# IndicationBoard.net
KiCad netlist of a schematic drawn in Altium Designer
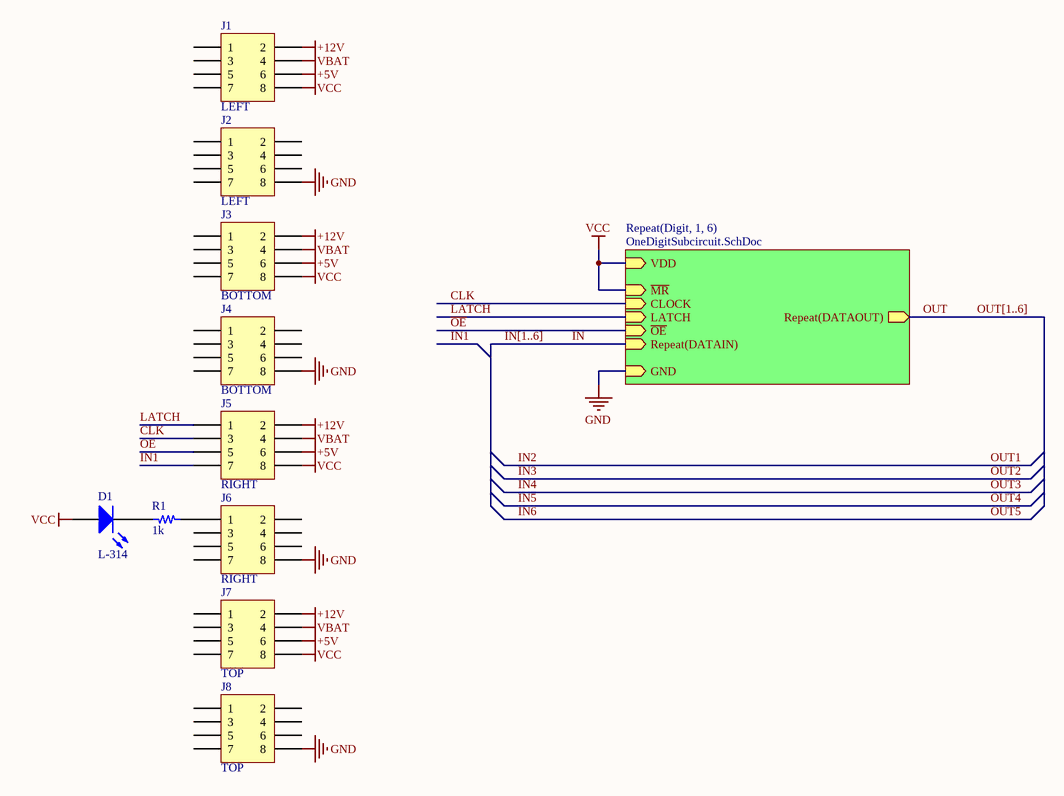
[diagram p0: IndicationBoard.SchDoc]

(export (version "E")
  (design (tool "Eeschema 10.0.6"))
  (components
    (comp (ref "D1")
      (value "L-314")
      (footprint "LED 3mm")
      (description "3-mm LED")
      (fields (field (name "AUTHOR") "oiezhov"))
      (libsource (lib "Library") (part "LED"))
    )
    (comp (ref "J1")
      (value "LEFT")
      (footprint "PBDM-8")
      (description "2x4-pin header, pitch 2.54 mm")
      (fields (field (name "PARTNUMBER") "PBDM-8") (field (name "AUTHOR") "oiezhov"))
      (libsource (lib "Library") (part "8-pin dual row connector"))
    )
    (comp (ref "J2")
      (value "LEFT")
      (footprint "PBDM-8")
      (description "2x4-pin header, pitch 2.54 mm")
      (fields (field (name "PARTNUMBER") "PBDM-8") (field (name "AUTHOR") "oiezhov"))
      (libsource (lib "Library") (part "8-pin dual row connector"))
    )
    (comp (ref "J3")
      (value "BOTTOM")
      (footprint "PBDM-8")
      (description "2x4-pin header, pitch 2.54 mm")
      (fields (field (name "PARTNUMBER") "PBDM-8") (field (name "AUTHOR") "oiezhov"))
      (libsource (lib "Library") (part "8-pin dual row connector"))
    )
    (comp (ref "J4")
      (value "BOTTOM")
      (footprint "PBDM-8")
      (description "2x4-pin header, pitch 2.54 mm")
      (fields (field (name "PARTNUMBER") "PBDM-8") (field (name "AUTHOR") "oiezhov"))
      (libsource (lib "Library") (part "8-pin dual row connector"))
    )
    (comp (ref "J5")
      (value "RIGHT")
      (footprint "PBDM-8")
      (description "2x4-pin header, pitch 2.54 mm")
      (fields (field (name "PARTNUMBER") "PBDM-8") (field (name "AUTHOR") "oiezhov"))
      (libsource (lib "Library") (part "8-pin dual row connector"))
    )
    (comp (ref "J6")
      (value "RIGHT")
      (footprint "PBDM-8")
      (description "2x4-pin header, pitch 2.54 mm")
      (fields (field (name "PARTNUMBER") "PBDM-8") (field (name "AUTHOR") "oiezhov"))
      (libsource (lib "Library") (part "8-pin dual row connector"))
    )
    (comp (ref "J7")
      (value "TOP")
      (footprint "PBDM-8")
      (description "2x4-pin header, pitch 2.54 mm")
      (fields (field (name "PARTNUMBER") "PBDM-8") (field (name "AUTHOR") "oiezhov"))
      (libsource (lib "Library") (part "8-pin dual row connector"))
    )
    (comp (ref "J8")
      (value "TOP")
      (footprint "PBDM-8")
      (description "2x4-pin header, pitch 2.54 mm")
      (fields (field (name "PARTNUMBER") "PBDM-8") (field (name "AUTHOR") "oiezhov"))
      (libsource (lib "Library") (part "8-pin dual row connector"))
    )
    (comp (ref "R1")
      (value "1k")
      (footprint "RES0402")
      (description "Ceramic chip resistor")
      (fields (field (name "PARTNUMBER") "RES0402") (field (name "AUTHOR") "oiezhov"))
      (libsource (lib "Library") (part "Resistor"))
    )
  )
  (nets
    (net (code "2") (name "+5V") (class "Default")
      (node (ref "J1") (pin "6") (pinfunction "6_6") (pintype "passive"))
      (node (ref "J3") (pin "6") (pinfunction "6_6") (pintype "passive"))
      (node (ref "J5") (pin "6") (pinfunction "6_6") (pintype "passive"))
      (node (ref "J7") (pin "6") (pinfunction "6_6") (pintype "passive"))
    )
    (net (code "3") (name "+12V") (class "Default")
      (node (ref "J1") (pin "2") (pinfunction "2_2") (pintype "passive"))
      (node (ref "J3") (pin "2") (pinfunction "2_2") (pintype "passive"))
      (node (ref "J5") (pin "2") (pinfunction "2_2") (pintype "passive"))
      (node (ref "J7") (pin "2") (pinfunction "2_2") (pintype "passive"))
    )
    (net (code "4") (name "/CLK") (class "Default")
      (node (ref "J5") (pin "3") (pinfunction "3_3") (pintype "passive"))
    )
    (net (code "6") (name "/IN1") (class "Default")
      (node (ref "J5") (pin "7") (pinfunction "7_7") (pintype "passive"))
    )
    (net (code "13") (name "/LATCH") (class "Default")
      (node (ref "J5") (pin "1") (pinfunction "1_1") (pintype "passive"))
    )
    (net (code "16") (name "/~{OE}") (class "Default")
      (node (ref "J5") (pin "5") (pinfunction "5_5") (pintype "passive"))
    )
    (net (code "17") (name "GND") (class "Default")
      (node (ref "J2") (pin "8") (pinfunction "8_8") (pintype "passive"))
      (node (ref "J4") (pin "8") (pinfunction "8_8") (pintype "passive"))
      (node (ref "J6") (pin "8") (pinfunction "8_8") (pintype "passive"))
      (node (ref "J8") (pin "8") (pinfunction "8_8") (pintype "passive"))
    )
    (net (code "18") (name "Net-(D1-Pad1)") (class "Default")
      (node (ref "D1") (pin "1") (pinfunction "1_1") (pintype "passive"))
      (node (ref "R1") (pin "1") (pinfunction "1_1") (pintype "passive"))
    )
    (net (code "19") (name "Net-(J6-Pad1)") (class "Default")
      (node (ref "J6") (pin "1") (pinfunction "1_1") (pintype "passive"))
      (node (ref "R1") (pin "2") (pinfunction "2_2") (pintype "passive"))
    )
    (net (code "20") (name "VBAT") (class "Default")
      (node (ref "J1") (pin "4") (pinfunction "4_4") (pintype "passive"))
      (node (ref "J3") (pin "4") (pinfunction "4_4") (pintype "passive"))
      (node (ref "J5") (pin "4") (pinfunction "4_4") (pintype "passive"))
      (node (ref "J7") (pin "4") (pinfunction "4_4") (pintype "passive"))
    )
    (net (code "21") (name "VCC") (class "Default")
      (node (ref "D1") (pin "2") (pinfunction "2_2") (pintype "passive"))
      (node (ref "J1") (pin "8") (pinfunction "8_8") (pintype "passive"))
      (node (ref "J3") (pin "8") (pinfunction "8_8") (pintype "passive"))
      (node (ref "J5") (pin "8") (pinfunction "8_8") (pintype "passive"))
      (node (ref "J7") (pin "8") (pinfunction "8_8") (pintype "passive"))
    )
    (net (code "22") (name "unconnected-(J1-Pad1)") (class "Default")
      (node (ref "J1") (pin "1") (pinfunction "1_1") (pintype "passive"))
    )
    (net (code "23") (name "unconnected-(J1-Pad3)") (class "Default")
      (node (ref "J1") (pin "3") (pinfunction "3_3") (pintype "passive"))
    )
    (net (code "24") (name "unconnected-(J1-Pad5)") (class "Default")
      (node (ref "J1") (pin "5") (pinfunction "5_5") (pintype "passive"))
    )
    (net (code "25") (name "unconnected-(J1-Pad7)") (class "Default")
      (node (ref "J1") (pin "7") (pinfunction "7_7") (pintype "passive"))
    )
    (net (code "26") (name "unconnected-(J2-Pad1)") (class "Default")
      (node (ref "J2") (pin "1") (pinfunction "1_1") (pintype "passive"))
    )
    (net (code "27") (name "unconnected-(J2-Pad2)") (class "Default")
      (node (ref "J2") (pin "2") (pinfunction "2_2") (pintype "passive"))
    )
    (net (code "28") (name "unconnected-(J2-Pad3)") (class "Default")
      (node (ref "J2") (pin "3") (pinfunction "3_3") (pintype "passive"))
    )
    (net (code "29") (name "unconnected-(J2-Pad4)") (class "Default")
      (node (ref "J2") (pin "4") (pinfunction "4_4") (pintype "passive"))
    )
    (net (code "30") (name "unconnected-(J2-Pad5)") (class "Default")
      (node (ref "J2") (pin "5") (pinfunction "5_5") (pintype "passive"))
    )
    (net (code "31") (name "unconnected-(J2-Pad6)") (class "Default")
      (node (ref "J2") (pin "6") (pinfunction "6_6") (pintype "passive"))
    )
    (net (code "32") (name "unconnected-(J2-Pad7)") (class "Default")
      (node (ref "J2") (pin "7") (pinfunction "7_7") (pintype "passive"))
    )
    (net (code "33") (name "unconnected-(J3-Pad1)") (class "Default")
      (node (ref "J3") (pin "1") (pinfunction "1_1") (pintype "passive"))
    )
    (net (code "34") (name "unconnected-(J3-Pad3)") (class "Default")
      (node (ref "J3") (pin "3") (pinfunction "3_3") (pintype "passive"))
    )
    (net (code "35") (name "unconnected-(J3-Pad5)") (class "Default")
      (node (ref "J3") (pin "5") (pinfunction "5_5") (pintype "passive"))
    )
    (net (code "36") (name "unconnected-(J3-Pad7)") (class "Default")
      (node (ref "J3") (pin "7") (pinfunction "7_7") (pintype "passive"))
    )
    (net (code "37") (name "unconnected-(J4-Pad1)") (class "Default")
      (node (ref "J4") (pin "1") (pinfunction "1_1") (pintype "passive"))
    )
    (net (code "38") (name "unconnected-(J4-Pad2)") (class "Default")
      (node (ref "J4") (pin "2") (pinfunction "2_2") (pintype "passive"))
    )
    (net (code "39") (name "unconnected-(J4-Pad3)") (class "Default")
      (node (ref "J4") (pin "3") (pinfunction "3_3") (pintype "passive"))
    )
    (net (code "40") (name "unconnected-(J4-Pad4)") (class "Default")
      (node (ref "J4") (pin "4") (pinfunction "4_4") (pintype "passive"))
    )
    (net (code "41") (name "unconnected-(J4-Pad5)") (class "Default")
      (node (ref "J4") (pin "5") (pinfunction "5_5") (pintype "passive"))
    )
    (net (code "42") (name "unconnected-(J4-Pad6)") (class "Default")
      (node (ref "J4") (pin "6") (pinfunction "6_6") (pintype "passive"))
    )
    (net (code "43") (name "unconnected-(J4-Pad7)") (class "Default")
      (node (ref "J4") (pin "7") (pinfunction "7_7") (pintype "passive"))
    )
    (net (code "44") (name "unconnected-(J6-Pad2)") (class "Default")
      (node (ref "J6") (pin "2") (pinfunction "2_2") (pintype "passive"))
    )
    (net (code "45") (name "unconnected-(J6-Pad3)") (class "Default")
      (node (ref "J6") (pin "3") (pinfunction "3_3") (pintype "passive"))
    )
    (net (code "46") (name "unconnected-(J6-Pad4)") (class "Default")
      (node (ref "J6") (pin "4") (pinfunction "4_4") (pintype "passive"))
    )
    (net (code "47") (name "unconnected-(J6-Pad5)") (class "Default")
      (node (ref "J6") (pin "5") (pinfunction "5_5") (pintype "passive"))
    )
    (net (code "48") (name "unconnected-(J6-Pad6)") (class "Default")
      (node (ref "J6") (pin "6") (pinfunction "6_6") (pintype "passive"))
    )
    (net (code "49") (name "unconnected-(J6-Pad7)") (class "Default")
      (node (ref "J6") (pin "7") (pinfunction "7_7") (pintype "passive"))
    )
    (net (code "50") (name "unconnected-(J7-Pad1)") (class "Default")
      (node (ref "J7") (pin "1") (pinfunction "1_1") (pintype "passive"))
    )
    (net (code "51") (name "unconnected-(J7-Pad3)") (class "Default")
      (node (ref "J7") (pin "3") (pinfunction "3_3") (pintype "passive"))
    )
    (net (code "52") (name "unconnected-(J7-Pad5)") (class "Default")
      (node (ref "J7") (pin "5") (pinfunction "5_5") (pintype "passive"))
    )
    (net (code "53") (name "unconnected-(J7-Pad7)") (class "Default")
      (node (ref "J7") (pin "7") (pinfunction "7_7") (pintype "passive"))
    )
    (net (code "54") (name "unconnected-(J8-Pad1)") (class "Default")
      (node (ref "J8") (pin "1") (pinfunction "1_1") (pintype "passive"))
    )
    (net (code "55") (name "unconnected-(J8-Pad2)") (class "Default")
      (node (ref "J8") (pin "2") (pinfunction "2_2") (pintype "passive"))
    )
    (net (code "56") (name "unconnected-(J8-Pad3)") (class "Default")
      (node (ref "J8") (pin "3") (pinfunction "3_3") (pintype "passive"))
    )
    (net (code "57") (name "unconnected-(J8-Pad4)") (class "Default")
      (node (ref "J8") (pin "4") (pinfunction "4_4") (pintype "passive"))
    )
    (net (code "58") (name "unconnected-(J8-Pad5)") (class "Default")
      (node (ref "J8") (pin "5") (pinfunction "5_5") (pintype "passive"))
    )
    (net (code "59") (name "unconnected-(J8-Pad6)") (class "Default")
      (node (ref "J8") (pin "6") (pinfunction "6_6") (pintype "passive"))
    )
    (net (code "60") (name "unconnected-(J8-Pad7)") (class "Default")
      (node (ref "J8") (pin "7") (pinfunction "7_7") (pintype "passive"))
    )
  )
)
